# scarlet.net
KiCad netlist of a schematic drawn in EAGLE
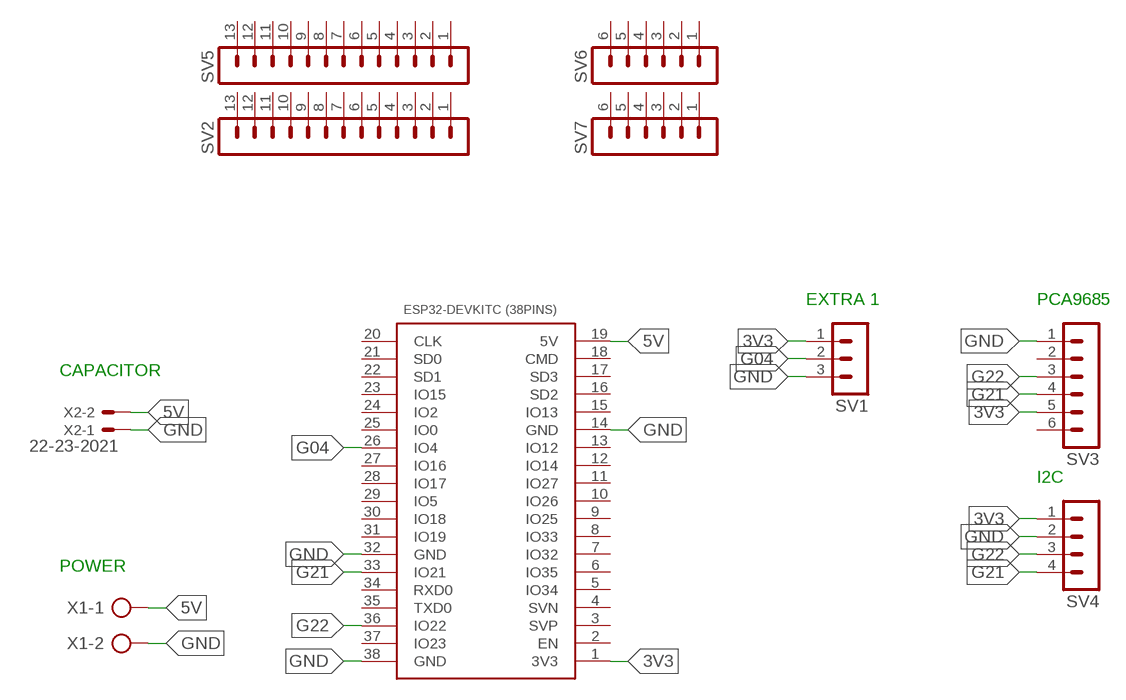
[diagram p0: schematic, sheet 1]

(export (version "E")
  (design (tool "Eeschema 10.0.6"))
  (components
    (comp (ref "ESP32-DEVKITC(38PINS)1")
      (value "ESP32DEVKITC_38PINS")
      (footprint "eagle-import:ESP32-DEVKITC")
      (libsource (lib "eagle-import") (part "ESP32DEVKITC_38PINS"))
    )
    (comp (ref "SV1")
      (value "MA03-1")
      (footprint "eagle-import:MA03-1")
      (libsource (lib "eagle-import") (part "MA03-1"))
    )
    (comp (ref "SV2")
      (value "MA13-1")
      (footprint "eagle-import:MA13-1")
      (libsource (lib "eagle-import") (part "MA13-1"))
    )
    (comp (ref "SV3")
      (value "MA06-1")
      (footprint "eagle-import:MA06-1")
      (libsource (lib "eagle-import") (part "MA06-1"))
    )
    (comp (ref "SV4")
      (value "MA04-1")
      (footprint "eagle-import:MA04-1")
      (libsource (lib "eagle-import") (part "MA04-1"))
    )
    (comp (ref "SV5")
      (value "MA13-1")
      (footprint "eagle-import:MA13-1")
      (libsource (lib "eagle-import") (part "MA13-1"))
    )
    (comp (ref "SV6")
      (value "MA06-1")
      (footprint "eagle-import:MA06-1")
      (libsource (lib "eagle-import") (part "MA06-1"))
    )
    (comp (ref "SV7")
      (value "MA06-1")
      (footprint "eagle-import:MA06-1")
      (libsource (lib "eagle-import") (part "MA06-1"))
    )
    (comp (ref "X1")
      (value "AK300/2")
      (footprint "eagle-import:AK300_2")
      (libsource (lib "eagle-import") (part "AK300/2"))
    )
    (comp (ref "X2")
      (value "22-23-2021")
      (footprint "eagle-import:22-23-2021")
      (fields (field (name "MF") "MOLEX"))
      (libsource (lib "eagle-import") (part "22-23-2021"))
    )
  )
  (nets
    (net (code "1") (name "3V3") (class "Default")
      (node (ref "ESP32-DEVKITC(38PINS)1") (pin "1") (pinfunction "3V3_1") (pintype "bidirectional"))
      (node (ref "SV1") (pin "1") (pinfunction "1_1") (pintype "passive"))
      (node (ref "SV3") (pin "5") (pinfunction "5_5") (pintype "passive"))
      (node (ref "SV4") (pin "1") (pinfunction "1_1") (pintype "passive"))
    )
    (net (code "2") (name "5V") (class "Default")
      (node (ref "ESP32-DEVKITC(38PINS)1") (pin "19") (pinfunction "5V_19") (pintype "bidirectional"))
      (node (ref "X1") (pin "1") (pinfunction "KL_1") (pintype "passive"))
      (node (ref "X2") (pin "2") (pinfunction "S_2") (pintype "passive"))
    )
    (net (code "3") (name "G04") (class "Default")
      (node (ref "ESP32-DEVKITC(38PINS)1") (pin "26") (pinfunction "IO4_26") (pintype "bidirectional"))
      (node (ref "SV1") (pin "2") (pinfunction "2_2") (pintype "passive"))
    )
    (net (code "4") (name "G21") (class "Default")
      (node (ref "ESP32-DEVKITC(38PINS)1") (pin "33") (pinfunction "IO21_33") (pintype "bidirectional"))
      (node (ref "SV3") (pin "4") (pinfunction "4_4") (pintype "passive"))
      (node (ref "SV4") (pin "4") (pinfunction "4_4") (pintype "passive"))
    )
    (net (code "5") (name "G22") (class "Default")
      (node (ref "ESP32-DEVKITC(38PINS)1") (pin "36") (pinfunction "IO22_36") (pintype "bidirectional"))
      (node (ref "SV3") (pin "3") (pinfunction "3_3") (pintype "passive"))
      (node (ref "SV4") (pin "3") (pinfunction "3_3") (pintype "passive"))
    )
    (net (code "6") (name "GND") (class "Default")
      (node (ref "ESP32-DEVKITC(38PINS)1") (pin "14") (pinfunction "GND_14") (pintype "bidirectional"))
      (node (ref "ESP32-DEVKITC(38PINS)1") (pin "32") (pinfunction "GND_32") (pintype "bidirectional"))
      (node (ref "ESP32-DEVKITC(38PINS)1") (pin "38") (pinfunction "GND_38") (pintype "bidirectional"))
      (node (ref "SV1") (pin "3") (pinfunction "3_3") (pintype "passive"))
      (node (ref "SV3") (pin "1") (pinfunction "1_1") (pintype "passive"))
      (node (ref "SV4") (pin "2") (pinfunction "2_2") (pintype "passive"))
      (node (ref "X1") (pin "2") (pinfunction "KL_2") (pintype "passive"))
      (node (ref "X2") (pin "1") (pinfunction "S_1") (pintype "passive"))
    )
    (net (code "7") (name "unconnected-(ESP32-DEVKITC(38PINS)1-CLK-Pad20)") (class "Default")
      (node (ref "ESP32-DEVKITC(38PINS)1") (pin "20") (pinfunction "CLK_20") (pintype "bidirectional"))
    )
    (net (code "8") (name "unconnected-(ESP32-DEVKITC(38PINS)1-CMD-Pad18)") (class "Default")
      (node (ref "ESP32-DEVKITC(38PINS)1") (pin "18") (pinfunction "CMD_18") (pintype "bidirectional"))
    )
    (net (code "9") (name "unconnected-(ESP32-DEVKITC(38PINS)1-EN-Pad2)") (class "Default")
      (node (ref "ESP32-DEVKITC(38PINS)1") (pin "2") (pinfunction "EN_2") (pintype "bidirectional"))
    )
    (net (code "10") (name "unconnected-(ESP32-DEVKITC(38PINS)1-IO0-Pad25)") (class "Default")
      (node (ref "ESP32-DEVKITC(38PINS)1") (pin "25") (pinfunction "IO0_25") (pintype "bidirectional"))
    )
    (net (code "11") (name "unconnected-(ESP32-DEVKITC(38PINS)1-IO2-Pad24)") (class "Default")
      (node (ref "ESP32-DEVKITC(38PINS)1") (pin "24") (pinfunction "IO2_24") (pintype "bidirectional"))
    )
    (net (code "12") (name "unconnected-(ESP32-DEVKITC(38PINS)1-IO5-Pad29)") (class "Default")
      (node (ref "ESP32-DEVKITC(38PINS)1") (pin "29") (pinfunction "IO5_29") (pintype "bidirectional"))
    )
    (net (code "13") (name "unconnected-(ESP32-DEVKITC(38PINS)1-IO12-Pad13)") (class "Default")
      (node (ref "ESP32-DEVKITC(38PINS)1") (pin "13") (pinfunction "IO12_13") (pintype "bidirectional"))
    )
    (net (code "14") (name "unconnected-(ESP32-DEVKITC(38PINS)1-IO13-Pad15)") (class "Default")
      (node (ref "ESP32-DEVKITC(38PINS)1") (pin "15") (pinfunction "IO13_15") (pintype "bidirectional"))
    )
    (net (code "15") (name "unconnected-(ESP32-DEVKITC(38PINS)1-IO14-Pad12)") (class "Default")
      (node (ref "ESP32-DEVKITC(38PINS)1") (pin "12") (pinfunction "IO14_12") (pintype "bidirectional"))
    )
    (net (code "16") (name "unconnected-(ESP32-DEVKITC(38PINS)1-IO15-Pad23)") (class "Default")
      (node (ref "ESP32-DEVKITC(38PINS)1") (pin "23") (pinfunction "IO15_23") (pintype "bidirectional"))
    )
    (net (code "17") (name "unconnected-(ESP32-DEVKITC(38PINS)1-IO16-Pad27)") (class "Default")
      (node (ref "ESP32-DEVKITC(38PINS)1") (pin "27") (pinfunction "IO16_27") (pintype "bidirectional"))
    )
    (net (code "18") (name "unconnected-(ESP32-DEVKITC(38PINS)1-IO17-Pad28)") (class "Default")
      (node (ref "ESP32-DEVKITC(38PINS)1") (pin "28") (pinfunction "IO17_28") (pintype "bidirectional"))
    )
    (net (code "19") (name "unconnected-(ESP32-DEVKITC(38PINS)1-IO18-Pad30)") (class "Default")
      (node (ref "ESP32-DEVKITC(38PINS)1") (pin "30") (pinfunction "IO18_30") (pintype "bidirectional"))
    )
    (net (code "20") (name "unconnected-(ESP32-DEVKITC(38PINS)1-IO19-Pad31)") (class "Default")
      (node (ref "ESP32-DEVKITC(38PINS)1") (pin "31") (pinfunction "IO19_31") (pintype "bidirectional"))
    )
    (net (code "21") (name "unconnected-(ESP32-DEVKITC(38PINS)1-IO23-Pad37)") (class "Default")
      (node (ref "ESP32-DEVKITC(38PINS)1") (pin "37") (pinfunction "IO23_37") (pintype "bidirectional"))
    )
    (net (code "22") (name "unconnected-(ESP32-DEVKITC(38PINS)1-IO25-Pad9)") (class "Default")
      (node (ref "ESP32-DEVKITC(38PINS)1") (pin "9") (pinfunction "IO25_9") (pintype "bidirectional"))
    )
    (net (code "23") (name "unconnected-(ESP32-DEVKITC(38PINS)1-IO26-Pad10)") (class "Default")
      (node (ref "ESP32-DEVKITC(38PINS)1") (pin "10") (pinfunction "IO26_10") (pintype "bidirectional"))
    )
    (net (code "24") (name "unconnected-(ESP32-DEVKITC(38PINS)1-IO27-Pad11)") (class "Default")
      (node (ref "ESP32-DEVKITC(38PINS)1") (pin "11") (pinfunction "IO27_11") (pintype "bidirectional"))
    )
    (net (code "25") (name "unconnected-(ESP32-DEVKITC(38PINS)1-IO32-Pad7)") (class "Default")
      (node (ref "ESP32-DEVKITC(38PINS)1") (pin "7") (pinfunction "IO32_7") (pintype "bidirectional"))
    )
    (net (code "26") (name "unconnected-(ESP32-DEVKITC(38PINS)1-IO33-Pad8)") (class "Default")
      (node (ref "ESP32-DEVKITC(38PINS)1") (pin "8") (pinfunction "IO33_8") (pintype "bidirectional"))
    )
    (net (code "27") (name "unconnected-(ESP32-DEVKITC(38PINS)1-IO34-Pad5)") (class "Default")
      (node (ref "ESP32-DEVKITC(38PINS)1") (pin "5") (pinfunction "IO34_5") (pintype "bidirectional"))
    )
    (net (code "28") (name "unconnected-(ESP32-DEVKITC(38PINS)1-IO35-Pad6)") (class "Default")
      (node (ref "ESP32-DEVKITC(38PINS)1") (pin "6") (pinfunction "IO35_6") (pintype "bidirectional"))
    )
    (net (code "29") (name "unconnected-(ESP32-DEVKITC(38PINS)1-RXD0-Pad34)") (class "Default")
      (node (ref "ESP32-DEVKITC(38PINS)1") (pin "34") (pinfunction "RXD0_34") (pintype "bidirectional"))
    )
    (net (code "30") (name "unconnected-(ESP32-DEVKITC(38PINS)1-SD0-Pad21)") (class "Default")
      (node (ref "ESP32-DEVKITC(38PINS)1") (pin "21") (pinfunction "SD0_21") (pintype "bidirectional"))
    )
    (net (code "31") (name "unconnected-(ESP32-DEVKITC(38PINS)1-SD1-Pad22)") (class "Default")
      (node (ref "ESP32-DEVKITC(38PINS)1") (pin "22") (pinfunction "SD1_22") (pintype "bidirectional"))
    )
    (net (code "32") (name "unconnected-(ESP32-DEVKITC(38PINS)1-SD2-Pad16)") (class "Default")
      (node (ref "ESP32-DEVKITC(38PINS)1") (pin "16") (pinfunction "SD2_16") (pintype "bidirectional"))
    )
    (net (code "33") (name "unconnected-(ESP32-DEVKITC(38PINS)1-SD3-Pad17)") (class "Default")
      (node (ref "ESP32-DEVKITC(38PINS)1") (pin "17") (pinfunction "SD3_17") (pintype "bidirectional"))
    )
    (net (code "34") (name "unconnected-(ESP32-DEVKITC(38PINS)1-SVN-Pad4)") (class "Default")
      (node (ref "ESP32-DEVKITC(38PINS)1") (pin "4") (pinfunction "SVN_4") (pintype "bidirectional"))
    )
    (net (code "35") (name "unconnected-(ESP32-DEVKITC(38PINS)1-SVP-Pad3)") (class "Default")
      (node (ref "ESP32-DEVKITC(38PINS)1") (pin "3") (pinfunction "SVP_3") (pintype "bidirectional"))
    )
    (net (code "36") (name "unconnected-(ESP32-DEVKITC(38PINS)1-TXD0-Pad35)") (class "Default")
      (node (ref "ESP32-DEVKITC(38PINS)1") (pin "35") (pinfunction "TXD0_35") (pintype "bidirectional"))
    )
    (net (code "37") (name "unconnected-(SV2-Pad1)") (class "Default")
      (node (ref "SV2") (pin "1") (pinfunction "1_1") (pintype "passive"))
    )
    (net (code "38") (name "unconnected-(SV2-Pad2)") (class "Default")
      (node (ref "SV2") (pin "2") (pinfunction "2_2") (pintype "passive"))
    )
    (net (code "39") (name "unconnected-(SV2-Pad3)") (class "Default")
      (node (ref "SV2") (pin "3") (pinfunction "3_3") (pintype "passive"))
    )
    (net (code "40") (name "unconnected-(SV2-Pad4)") (class "Default")
      (node (ref "SV2") (pin "4") (pinfunction "4_4") (pintype "passive"))
    )
    (net (code "41") (name "unconnected-(SV2-Pad5)") (class "Default")
      (node (ref "SV2") (pin "5") (pinfunction "5_5") (pintype "passive"))
    )
    (net (code "42") (name "unconnected-(SV2-Pad6)") (class "Default")
      (node (ref "SV2") (pin "6") (pinfunction "6_6") (pintype "passive"))
    )
    (net (code "43") (name "unconnected-(SV2-Pad7)") (class "Default")
      (node (ref "SV2") (pin "7") (pinfunction "7_7") (pintype "passive"))
    )
    (net (code "44") (name "unconnected-(SV2-Pad8)") (class "Default")
      (node (ref "SV2") (pin "8") (pinfunction "8_8") (pintype "passive"))
    )
    (net (code "45") (name "unconnected-(SV2-Pad9)") (class "Default")
      (node (ref "SV2") (pin "9") (pinfunction "9_9") (pintype "passive"))
    )
    (net (code "46") (name "unconnected-(SV2-Pad10)") (class "Default")
      (node (ref "SV2") (pin "10") (pinfunction "10_10") (pintype "passive"))
    )
    (net (code "47") (name "unconnected-(SV2-Pad11)") (class "Default")
      (node (ref "SV2") (pin "11") (pinfunction "11_11") (pintype "passive"))
    )
    (net (code "48") (name "unconnected-(SV2-Pad12)") (class "Default")
      (node (ref "SV2") (pin "12") (pinfunction "12_12") (pintype "passive"))
    )
    (net (code "49") (name "unconnected-(SV2-Pad13)") (class "Default")
      (node (ref "SV2") (pin "13") (pinfunction "13_13") (pintype "passive"))
    )
    (net (code "50") (name "unconnected-(SV3-Pad2)") (class "Default")
      (node (ref "SV3") (pin "2") (pinfunction "2_2") (pintype "passive"))
    )
    (net (code "51") (name "unconnected-(SV3-Pad6)") (class "Default")
      (node (ref "SV3") (pin "6") (pinfunction "6_6") (pintype "passive"))
    )
    (net (code "52") (name "unconnected-(SV5-Pad1)") (class "Default")
      (node (ref "SV5") (pin "1") (pinfunction "1_1") (pintype "passive"))
    )
    (net (code "53") (name "unconnected-(SV5-Pad2)") (class "Default")
      (node (ref "SV5") (pin "2") (pinfunction "2_2") (pintype "passive"))
    )
    (net (code "54") (name "unconnected-(SV5-Pad3)") (class "Default")
      (node (ref "SV5") (pin "3") (pinfunction "3_3") (pintype "passive"))
    )
    (net (code "55") (name "unconnected-(SV5-Pad4)") (class "Default")
      (node (ref "SV5") (pin "4") (pinfunction "4_4") (pintype "passive"))
    )
    (net (code "56") (name "unconnected-(SV5-Pad5)") (class "Default")
      (node (ref "SV5") (pin "5") (pinfunction "5_5") (pintype "passive"))
    )
    (net (code "57") (name "unconnected-(SV5-Pad6)") (class "Default")
      (node (ref "SV5") (pin "6") (pinfunction "6_6") (pintype "passive"))
    )
    (net (code "58") (name "unconnected-(SV5-Pad7)") (class "Default")
      (node (ref "SV5") (pin "7") (pinfunction "7_7") (pintype "passive"))
    )
    (net (code "59") (name "unconnected-(SV5-Pad8)") (class "Default")
      (node (ref "SV5") (pin "8") (pinfunction "8_8") (pintype "passive"))
    )
    (net (code "60") (name "unconnected-(SV5-Pad9)") (class "Default")
      (node (ref "SV5") (pin "9") (pinfunction "9_9") (pintype "passive"))
    )
    (net (code "61") (name "unconnected-(SV5-Pad10)") (class "Default")
      (node (ref "SV5") (pin "10") (pinfunction "10_10") (pintype "passive"))
    )
    (net (code "62") (name "unconnected-(SV5-Pad11)") (class "Default")
      (node (ref "SV5") (pin "11") (pinfunction "11_11") (pintype "passive"))
    )
    (net (code "63") (name "unconnected-(SV5-Pad12)") (class "Default")
      (node (ref "SV5") (pin "12") (pinfunction "12_12") (pintype "passive"))
    )
    (net (code "64") (name "unconnected-(SV5-Pad13)") (class "Default")
      (node (ref "SV5") (pin "13") (pinfunction "13_13") (pintype "passive"))
    )
    (net (code "65") (name "unconnected-(SV6-Pad1)") (class "Default")
      (node (ref "SV6") (pin "1") (pinfunction "1_1") (pintype "passive"))
    )
    (net (code "66") (name "unconnected-(SV6-Pad2)") (class "Default")
      (node (ref "SV6") (pin "2") (pinfunction "2_2") (pintype "passive"))
    )
    (net (code "67") (name "unconnected-(SV6-Pad3)") (class "Default")
      (node (ref "SV6") (pin "3") (pinfunction "3_3") (pintype "passive"))
    )
    (net (code "68") (name "unconnected-(SV6-Pad4)") (class "Default")
      (node (ref "SV6") (pin "4") (pinfunction "4_4") (pintype "passive"))
    )
    (net (code "69") (name "unconnected-(SV6-Pad5)") (class "Default")
      (node (ref "SV6") (pin "5") (pinfunction "5_5") (pintype "passive"))
    )
    (net (code "70") (name "unconnected-(SV6-Pad6)") (class "Default")
      (node (ref "SV6") (pin "6") (pinfunction "6_6") (pintype "passive"))
    )
    (net (code "71") (name "unconnected-(SV7-Pad1)") (class "Default")
      (node (ref "SV7") (pin "1") (pinfunction "1_1") (pintype "passive"))
    )
    (net (code "72") (name "unconnected-(SV7-Pad2)") (class "Default")
      (node (ref "SV7") (pin "2") (pinfunction "2_2") (pintype "passive"))
    )
    (net (code "73") (name "unconnected-(SV7-Pad3)") (class "Default")
      (node (ref "SV7") (pin "3") (pinfunction "3_3") (pintype "passive"))
    )
    (net (code "74") (name "unconnected-(SV7-Pad4)") (class "Default")
      (node (ref "SV7") (pin "4") (pinfunction "4_4") (pintype "passive"))
    )
    (net (code "75") (name "unconnected-(SV7-Pad5)") (class "Default")
      (node (ref "SV7") (pin "5") (pinfunction "5_5") (pintype "passive"))
    )
    (net (code "76") (name "unconnected-(SV7-Pad6)") (class "Default")
      (node (ref "SV7") (pin "6") (pinfunction "6_6") (pintype "passive"))
    )
  )
)
